# jack_led_matrix.net
KiCad netlist of a schematic drawn in EAGLE
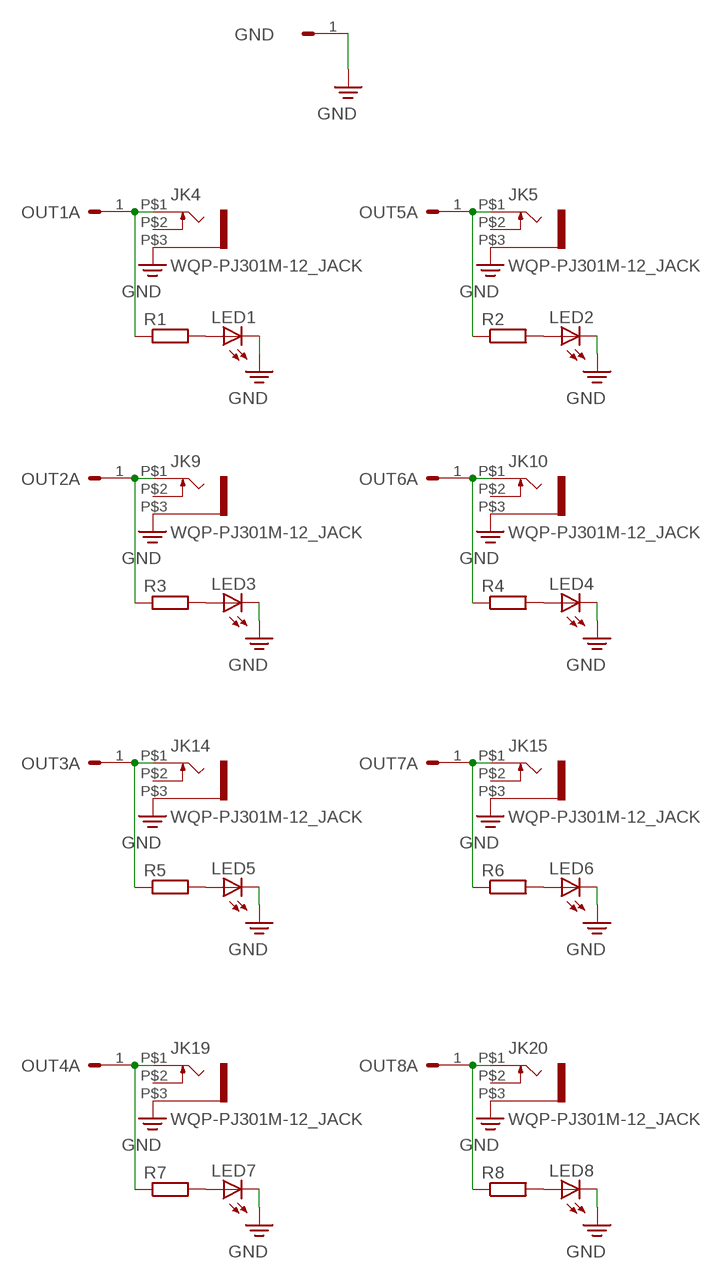
[diagram p0: schematic, sheet 1]

(export (version "E")
  (design (tool "Eeschema 10.0.6"))
  (components
    (comp (ref "GND")
      (value "HEADER/MALE/01")
      (footprint "eagle-import:HEADER_MALE_01")
      (fields (field (name "SPICEPREFIX") "X"))
      (libsource (lib "eagle-import") (part "HEADER/MALE/01"))
    )
    (comp (ref "JK4")
      (value "WQP-PJ301M-12_JACK")
      (footprint "eagle-import:WQP-PJ301M-12_JACK")
      (libsource (lib "eagle-import") (part "WQP-PJ301M-12_JACK"))
    )
    (comp (ref "JK5")
      (value "WQP-PJ301M-12_JACK")
      (footprint "eagle-import:WQP-PJ301M-12_JACK")
      (libsource (lib "eagle-import") (part "WQP-PJ301M-12_JACK"))
    )
    (comp (ref "JK9")
      (value "WQP-PJ301M-12_JACK")
      (footprint "eagle-import:WQP-PJ301M-12_JACK")
      (libsource (lib "eagle-import") (part "WQP-PJ301M-12_JACK"))
    )
    (comp (ref "JK10")
      (value "WQP-PJ301M-12_JACK")
      (footprint "eagle-import:WQP-PJ301M-12_JACK")
      (libsource (lib "eagle-import") (part "WQP-PJ301M-12_JACK"))
    )
    (comp (ref "JK14")
      (value "WQP-PJ301M-12_JACK")
      (footprint "eagle-import:WQP-PJ301M-12_JACK")
      (libsource (lib "eagle-import") (part "WQP-PJ301M-12_JACK"))
    )
    (comp (ref "JK15")
      (value "WQP-PJ301M-12_JACK")
      (footprint "eagle-import:WQP-PJ301M-12_JACK")
      (libsource (lib "eagle-import") (part "WQP-PJ301M-12_JACK"))
    )
    (comp (ref "JK19")
      (value "WQP-PJ301M-12_JACK")
      (footprint "eagle-import:WQP-PJ301M-12_JACK")
      (libsource (lib "eagle-import") (part "WQP-PJ301M-12_JACK"))
    )
    (comp (ref "JK20")
      (value "WQP-PJ301M-12_JACK")
      (footprint "eagle-import:WQP-PJ301M-12_JACK")
      (libsource (lib "eagle-import") (part "WQP-PJ301M-12_JACK"))
    )
    (comp (ref "LED1")
      (value "LED3MM")
      (footprint "eagle-import:LED3MM")
      (libsource (lib "eagle-import") (part "LED3MM"))
    )
    (comp (ref "LED2")
      (value "LED3MM")
      (footprint "eagle-import:LED3MM")
      (libsource (lib "eagle-import") (part "LED3MM"))
    )
    (comp (ref "LED3")
      (value "LED3MM")
      (footprint "eagle-import:LED3MM")
      (libsource (lib "eagle-import") (part "LED3MM"))
    )
    (comp (ref "LED4")
      (value "LED3MM")
      (footprint "eagle-import:LED3MM")
      (libsource (lib "eagle-import") (part "LED3MM"))
    )
    (comp (ref "LED5")
      (value "LED3MM")
      (footprint "eagle-import:LED3MM")
      (libsource (lib "eagle-import") (part "LED3MM"))
    )
    (comp (ref "LED6")
      (value "LED3MM")
      (footprint "eagle-import:LED3MM")
      (libsource (lib "eagle-import") (part "LED3MM"))
    )
    (comp (ref "LED7")
      (value "LED3MM")
      (footprint "eagle-import:LED3MM")
      (libsource (lib "eagle-import") (part "LED3MM"))
    )
    (comp (ref "LED8")
      (value "LED3MM")
      (footprint "eagle-import:LED3MM")
      (libsource (lib "eagle-import") (part "LED3MM"))
    )
    (comp (ref "OUT1A")
      (value "HEADER/MALE/01")
      (footprint "eagle-import:HEADER_MALE_01")
      (fields (field (name "SPICEPREFIX") "X"))
      (libsource (lib "eagle-import") (part "HEADER/MALE/01"))
    )
    (comp (ref "OUT2A")
      (value "HEADER/MALE/01")
      (footprint "eagle-import:HEADER_MALE_01")
      (fields (field (name "SPICEPREFIX") "X"))
      (libsource (lib "eagle-import") (part "HEADER/MALE/01"))
    )
    (comp (ref "OUT3A")
      (value "HEADER/MALE/01")
      (footprint "eagle-import:HEADER_MALE_01")
      (fields (field (name "SPICEPREFIX") "X"))
      (libsource (lib "eagle-import") (part "HEADER/MALE/01"))
    )
    (comp (ref "OUT4A")
      (value "HEADER/MALE/01")
      (footprint "eagle-import:HEADER_MALE_01")
      (fields (field (name "SPICEPREFIX") "X"))
      (libsource (lib "eagle-import") (part "HEADER/MALE/01"))
    )
    (comp (ref "OUT5A")
      (value "HEADER/MALE/01")
      (footprint "eagle-import:HEADER_MALE_01")
      (fields (field (name "SPICEPREFIX") "X"))
      (libsource (lib "eagle-import") (part "HEADER/MALE/01"))
    )
    (comp (ref "OUT6A")
      (value "HEADER/MALE/01")
      (footprint "eagle-import:HEADER_MALE_01")
      (fields (field (name "SPICEPREFIX") "X"))
      (libsource (lib "eagle-import") (part "HEADER/MALE/01"))
    )
    (comp (ref "OUT7A")
      (value "HEADER/MALE/01")
      (footprint "eagle-import:HEADER_MALE_01")
      (fields (field (name "SPICEPREFIX") "X"))
      (libsource (lib "eagle-import") (part "HEADER/MALE/01"))
    )
    (comp (ref "OUT8A")
      (value "HEADER/MALE/01")
      (footprint "eagle-import:HEADER_MALE_01")
      (fields (field (name "SPICEPREFIX") "X"))
      (libsource (lib "eagle-import") (part "HEADER/MALE/01"))
    )
    (comp (ref "R1")
      (value "RESISTORRESISTOR/UPRIGHT/7.5")
      (footprint "eagle-import:RESISTOR_7.5")
      (libsource (lib "eagle-import") (part "RESISTORRESISTOR/UPRIGHT/7.5"))
    )
    (comp (ref "R2")
      (value "RESISTORRESISTOR/UPRIGHT/7.5")
      (footprint "eagle-import:RESISTOR_7.5")
      (libsource (lib "eagle-import") (part "RESISTORRESISTOR/UPRIGHT/7.5"))
    )
    (comp (ref "R3")
      (value "RESISTORRESISTOR/UPRIGHT/7.5")
      (footprint "eagle-import:RESISTOR_7.5")
      (libsource (lib "eagle-import") (part "RESISTORRESISTOR/UPRIGHT/7.5"))
    )
    (comp (ref "R4")
      (value "RESISTORRESISTOR/UPRIGHT/7.5")
      (footprint "eagle-import:RESISTOR_7.5")
      (libsource (lib "eagle-import") (part "RESISTORRESISTOR/UPRIGHT/7.5"))
    )
    (comp (ref "R5")
      (value "RESISTORRESISTOR/UPRIGHT/7.5")
      (footprint "eagle-import:RESISTOR_7.5")
      (libsource (lib "eagle-import") (part "RESISTORRESISTOR/UPRIGHT/7.5"))
    )
    (comp (ref "R6")
      (value "RESISTORRESISTOR/UPRIGHT/7.5")
      (footprint "eagle-import:RESISTOR_7.5")
      (libsource (lib "eagle-import") (part "RESISTORRESISTOR/UPRIGHT/7.5"))
    )
    (comp (ref "R7")
      (value "RESISTORRESISTOR/UPRIGHT/7.5")
      (footprint "eagle-import:RESISTOR_7.5")
      (libsource (lib "eagle-import") (part "RESISTORRESISTOR/UPRIGHT/7.5"))
    )
    (comp (ref "R8")
      (value "RESISTORRESISTOR/UPRIGHT/7.5")
      (footprint "eagle-import:RESISTOR_7.5")
      (libsource (lib "eagle-import") (part "RESISTORRESISTOR/UPRIGHT/7.5"))
    )
  )
  (nets
    (net (code "1") (name "GND") (class "Default")
      (node (ref "GND") (pin "1") (pinfunction "3_1") (pintype "passive"))
      (node (ref "JK10") (pin "P$3") (pinfunction "1_P$3") (pintype "passive"))
      (node (ref "JK14") (pin "P$3") (pinfunction "1_P$3") (pintype "passive"))
      (node (ref "JK15") (pin "P$3") (pinfunction "1_P$3") (pintype "passive"))
      (node (ref "JK19") (pin "P$3") (pinfunction "1_P$3") (pintype "passive"))
      (node (ref "JK20") (pin "P$3") (pinfunction "1_P$3") (pintype "passive"))
      (node (ref "JK4") (pin "P$3") (pinfunction "1_P$3") (pintype "passive"))
      (node (ref "JK5") (pin "P$3") (pinfunction "1_P$3") (pintype "passive"))
      (node (ref "JK9") (pin "P$3") (pinfunction "1_P$3") (pintype "passive"))
      (node (ref "LED1") (pin "K") (pinfunction "C_K") (pintype "passive"))
      (node (ref "LED2") (pin "K") (pinfunction "C_K") (pintype "passive"))
      (node (ref "LED3") (pin "K") (pinfunction "C_K") (pintype "passive"))
      (node (ref "LED4") (pin "K") (pinfunction "C_K") (pintype "passive"))
      (node (ref "LED5") (pin "K") (pinfunction "C_K") (pintype "passive"))
      (node (ref "LED6") (pin "K") (pinfunction "C_K") (pintype "passive"))
      (node (ref "LED7") (pin "K") (pinfunction "C_K") (pintype "passive"))
      (node (ref "LED8") (pin "K") (pinfunction "C_K") (pintype "passive"))
    )
    (net (code "2") (name "Net-(JK4-2)") (class "Default")
      (node (ref "JK4") (pin "P$1") (pinfunction "2_P$1") (pintype "passive"))
      (node (ref "OUT1A") (pin "1") (pinfunction "3_1") (pintype "passive"))
      (node (ref "R1") (pin "1") (pinfunction "1_1") (pintype "passive"))
    )
    (net (code "3") (name "Net-(JK5-2)") (class "Default")
      (node (ref "JK5") (pin "P$1") (pinfunction "2_P$1") (pintype "passive"))
      (node (ref "OUT5A") (pin "1") (pinfunction "3_1") (pintype "passive"))
      (node (ref "R2") (pin "1") (pinfunction "1_1") (pintype "passive"))
    )
    (net (code "4") (name "Net-(JK9-2)") (class "Default")
      (node (ref "JK9") (pin "P$1") (pinfunction "2_P$1") (pintype "passive"))
      (node (ref "OUT2A") (pin "1") (pinfunction "3_1") (pintype "passive"))
      (node (ref "R3") (pin "1") (pinfunction "1_1") (pintype "passive"))
    )
    (net (code "5") (name "Net-(JK10-2)") (class "Default")
      (node (ref "JK10") (pin "P$1") (pinfunction "2_P$1") (pintype "passive"))
      (node (ref "OUT6A") (pin "1") (pinfunction "3_1") (pintype "passive"))
      (node (ref "R4") (pin "1") (pinfunction "1_1") (pintype "passive"))
    )
    (net (code "6") (name "Net-(JK14-2)") (class "Default")
      (node (ref "JK14") (pin "P$1") (pinfunction "2_P$1") (pintype "passive"))
      (node (ref "OUT3A") (pin "1") (pinfunction "3_1") (pintype "passive"))
      (node (ref "R5") (pin "1") (pinfunction "1_1") (pintype "passive"))
    )
    (net (code "7") (name "Net-(JK15-2)") (class "Default")
      (node (ref "JK15") (pin "P$1") (pinfunction "2_P$1") (pintype "passive"))
      (node (ref "OUT7A") (pin "1") (pinfunction "3_1") (pintype "passive"))
      (node (ref "R6") (pin "1") (pinfunction "1_1") (pintype "passive"))
    )
    (net (code "8") (name "Net-(JK19-2)") (class "Default")
      (node (ref "JK19") (pin "P$1") (pinfunction "2_P$1") (pintype "passive"))
      (node (ref "OUT4A") (pin "1") (pinfunction "3_1") (pintype "passive"))
      (node (ref "R7") (pin "1") (pinfunction "1_1") (pintype "passive"))
    )
    (net (code "9") (name "Net-(JK20-2)") (class "Default")
      (node (ref "JK20") (pin "P$1") (pinfunction "2_P$1") (pintype "passive"))
      (node (ref "OUT8A") (pin "1") (pinfunction "3_1") (pintype "passive"))
      (node (ref "R8") (pin "1") (pinfunction "1_1") (pintype "passive"))
    )
    (net (code "10") (name "Net-(LED1-PadA)") (class "Default")
      (node (ref "LED1") (pin "A") (pinfunction "A_A") (pintype "passive"))
      (node (ref "R1") (pin "2") (pinfunction "2_2") (pintype "passive"))
    )
    (net (code "11") (name "Net-(LED2-PadA)") (class "Default")
      (node (ref "LED2") (pin "A") (pinfunction "A_A") (pintype "passive"))
      (node (ref "R2") (pin "2") (pinfunction "2_2") (pintype "passive"))
    )
    (net (code "12") (name "Net-(LED3-PadA)") (class "Default")
      (node (ref "LED3") (pin "A") (pinfunction "A_A") (pintype "passive"))
      (node (ref "R3") (pin "2") (pinfunction "2_2") (pintype "passive"))
    )
    (net (code "13") (name "Net-(LED4-PadA)") (class "Default")
      (node (ref "LED4") (pin "A") (pinfunction "A_A") (pintype "passive"))
      (node (ref "R4") (pin "2") (pinfunction "2_2") (pintype "passive"))
    )
    (net (code "14") (name "Net-(LED5-PadA)") (class "Default")
      (node (ref "LED5") (pin "A") (pinfunction "A_A") (pintype "passive"))
      (node (ref "R5") (pin "2") (pinfunction "2_2") (pintype "passive"))
    )
    (net (code "15") (name "Net-(LED6-PadA)") (class "Default")
      (node (ref "LED6") (pin "A") (pinfunction "A_A") (pintype "passive"))
      (node (ref "R6") (pin "2") (pinfunction "2_2") (pintype "passive"))
    )
    (net (code "16") (name "Net-(LED7-PadA)") (class "Default")
      (node (ref "LED7") (pin "A") (pinfunction "A_A") (pintype "passive"))
      (node (ref "R7") (pin "2") (pinfunction "2_2") (pintype "passive"))
    )
    (net (code "17") (name "Net-(LED8-PadA)") (class "Default")
      (node (ref "LED8") (pin "A") (pinfunction "A_A") (pintype "passive"))
      (node (ref "R8") (pin "2") (pinfunction "2_2") (pintype "passive"))
    )
    (net (code "18") (name "unconnected-(JK4-3-PadP$2)") (class "Default")
      (node (ref "JK4") (pin "P$2") (pinfunction "3_P$2") (pintype "passive"))
    )
    (net (code "19") (name "unconnected-(JK5-3-PadP$2)") (class "Default")
      (node (ref "JK5") (pin "P$2") (pinfunction "3_P$2") (pintype "passive"))
    )
    (net (code "20") (name "unconnected-(JK9-3-PadP$2)") (class "Default")
      (node (ref "JK9") (pin "P$2") (pinfunction "3_P$2") (pintype "passive"))
    )
    (net (code "21") (name "unconnected-(JK10-3-PadP$2)") (class "Default")
      (node (ref "JK10") (pin "P$2") (pinfunction "3_P$2") (pintype "passive"))
    )
    (net (code "22") (name "unconnected-(JK14-3-PadP$2)") (class "Default")
      (node (ref "JK14") (pin "P$2") (pinfunction "3_P$2") (pintype "passive"))
    )
    (net (code "23") (name "unconnected-(JK15-3-PadP$2)") (class "Default")
      (node (ref "JK15") (pin "P$2") (pinfunction "3_P$2") (pintype "passive"))
    )
    (net (code "24") (name "unconnected-(JK19-3-PadP$2)") (class "Default")
      (node (ref "JK19") (pin "P$2") (pinfunction "3_P$2") (pintype "passive"))
    )
    (net (code "25") (name "unconnected-(JK20-3-PadP$2)") (class "Default")
      (node (ref "JK20") (pin "P$2") (pinfunction "3_P$2") (pintype "passive"))
    )
  )
)
